# clock_core.net
KiCad netlist of a schematic drawn in Altium Designer
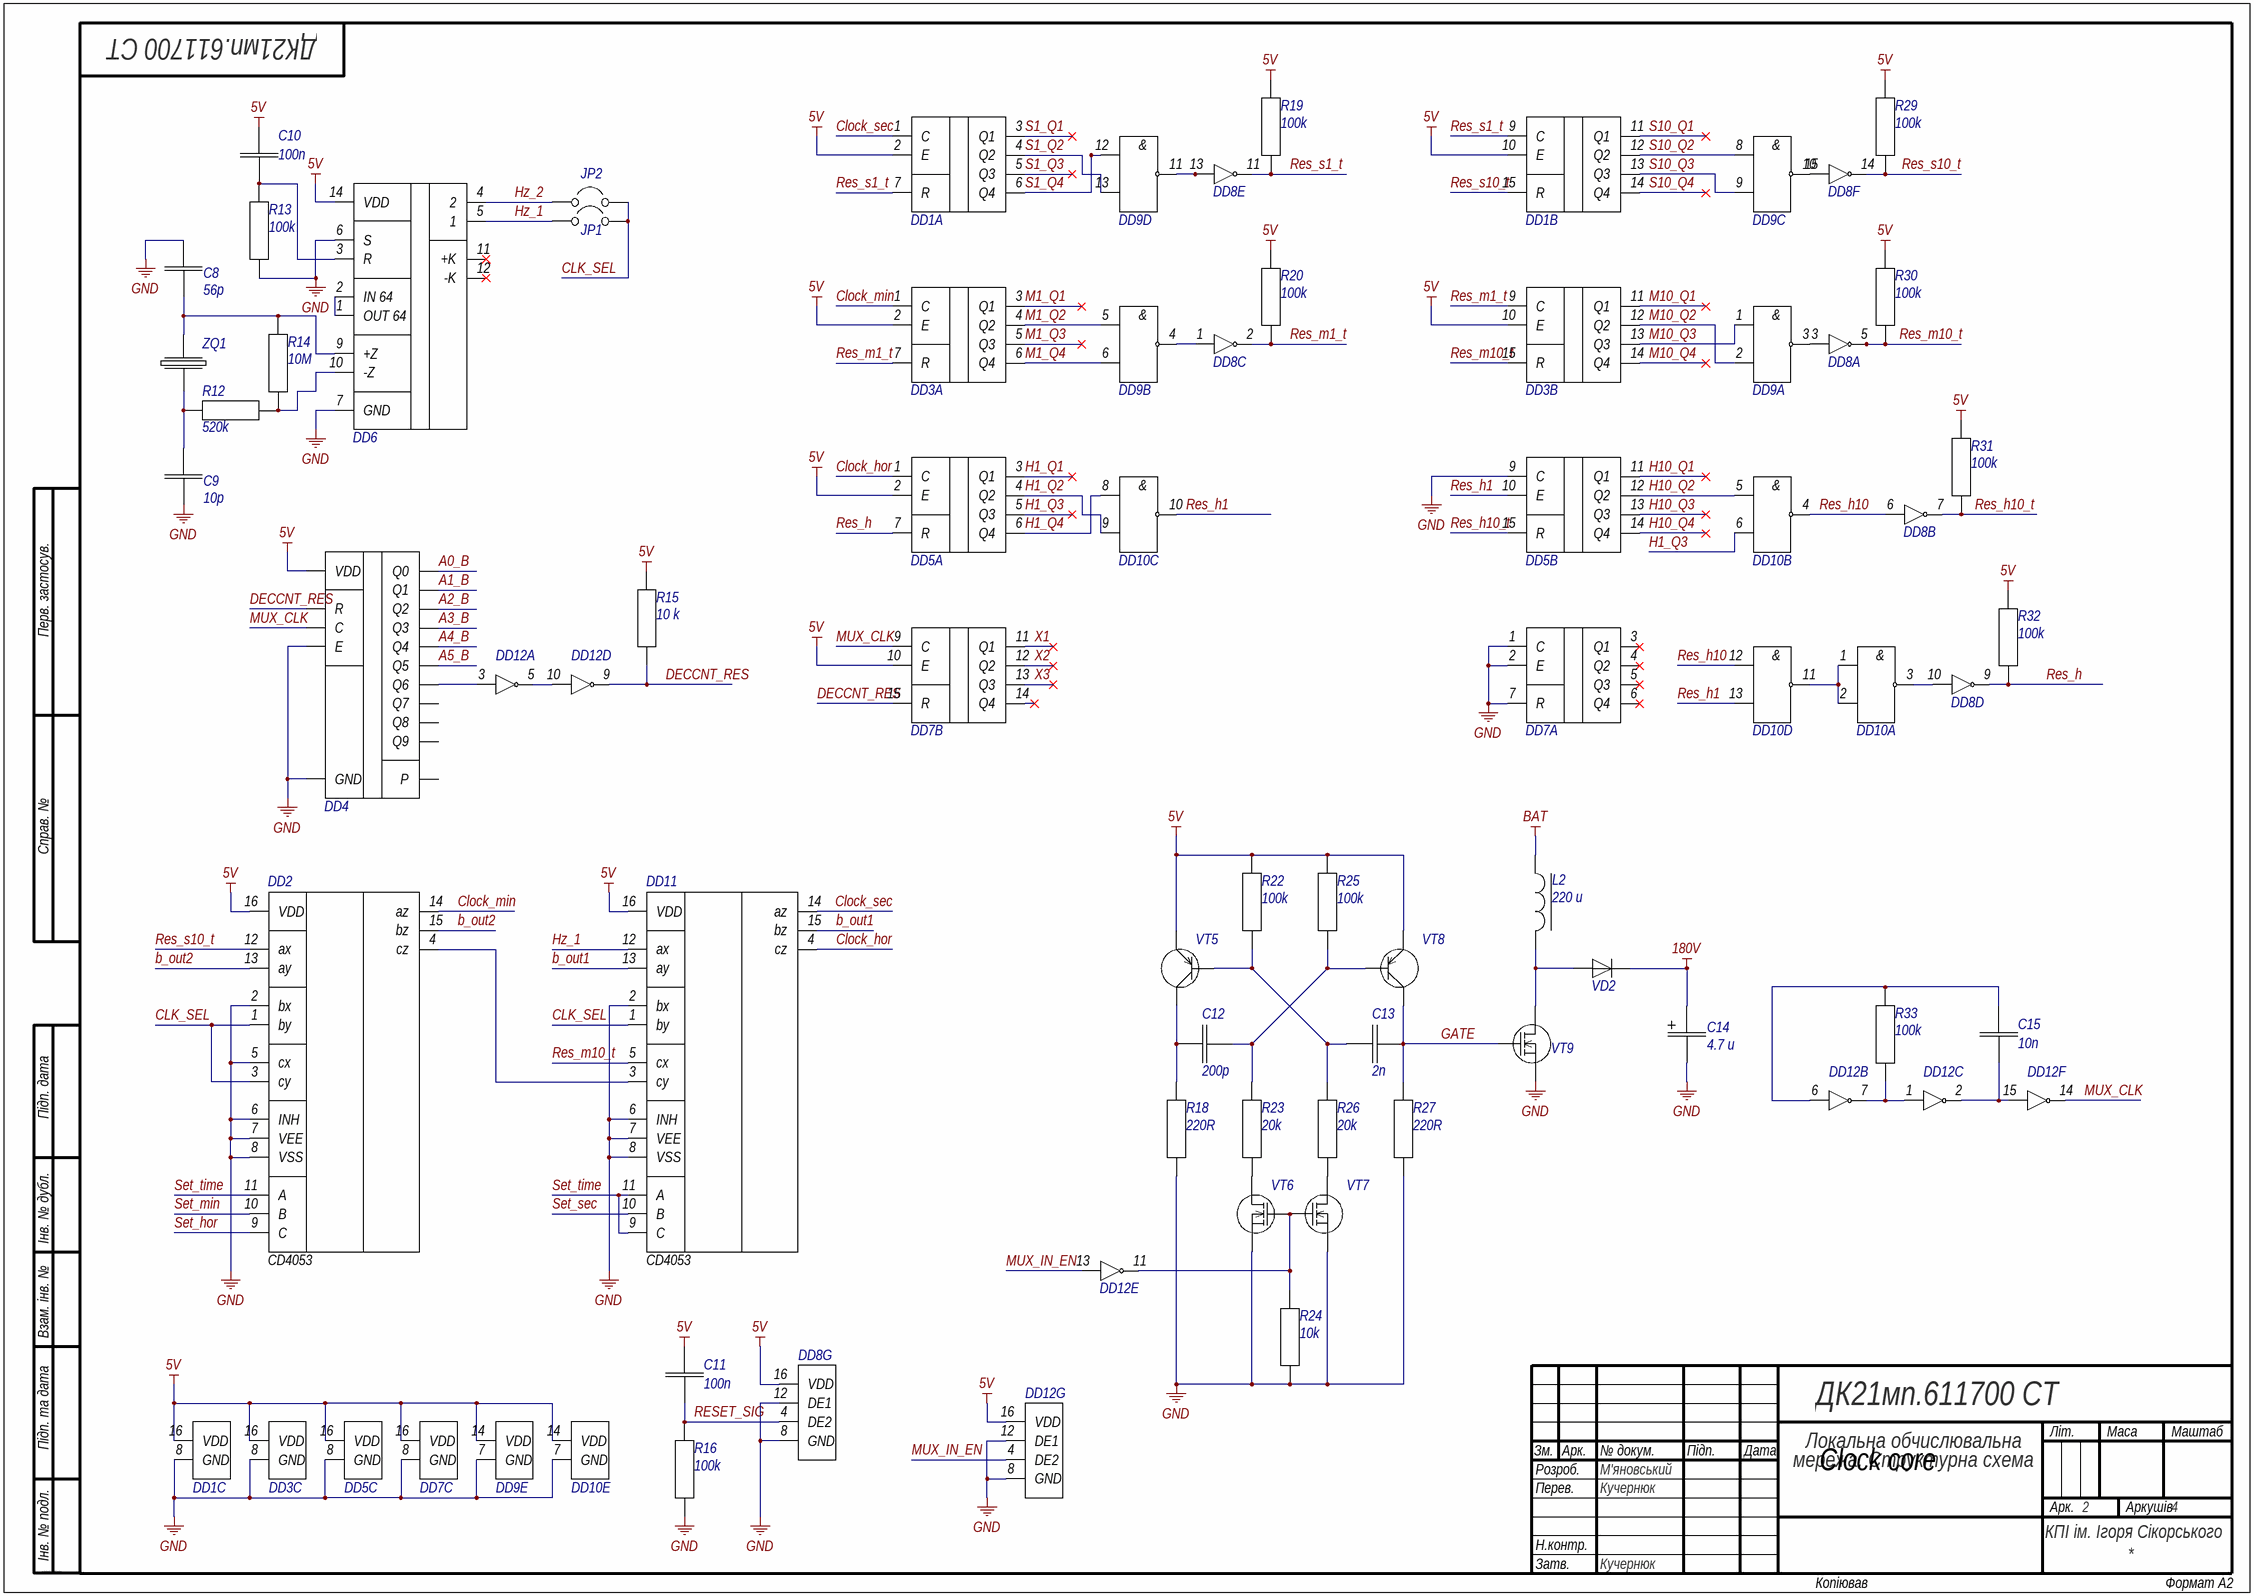
[diagram p0: clock_core.SchDoc]

(export (version "E")
  (design (tool "Eeschema 10.0.6"))
  (components
    (comp (ref "C8")
      (value "56p")
      (footprint "CAP_THT")
      (fields (field (name "Comment") "C"))
      (libsource (lib "Schlib1") (part "C"))
    )
    (comp (ref "C9")
      (value "10p")
      (footprint "CAP_THT")
      (fields (field (name "Comment") "C"))
      (libsource (lib "Schlib1") (part "C"))
    )
    (comp (ref "C10")
      (value "100n")
      (footprint "CAP_THT")
      (fields (field (name "Comment") "C"))
      (libsource (lib "Schlib1") (part "C"))
    )
    (comp (ref "C11")
      (value "100n")
      (footprint "CAP_THT")
      (fields (field (name "Comment") "C"))
      (libsource (lib "Schlib1") (part "C"))
    )
    (comp (ref "C12")
      (value "200p")
      (footprint "CAP_THT")
      (fields (field (name "Comment") "C"))
      (libsource (lib "Schlib1") (part "C"))
    )
    (comp (ref "C13")
      (value "2n")
      (footprint "CAP_THT")
      (fields (field (name "Comment") "C"))
      (libsource (lib "Schlib1") (part "C"))
    )
    (comp (ref "C14")
      (value "4.7 u")
      (footprint "CAP_HIGH_VOLT")
      (fields (field (name "Comment") "C+"))
      (libsource (lib "Schlib1") (part "C+"))
    )
    (comp (ref "C15")
      (value "10n")
      (footprint "CAP_THT")
      (fields (field (name "Comment") "C"))
      (libsource (lib "Schlib1") (part "C"))
    )
    (comp (ref "DD1") (value "К561ИЕ10") (footprint "DIP-16") (libsource (lib "Schlib1") (part "К561ИЕ10")))
    (comp (ref "DD2")
      (value "CD4053")
      (footprint "DIP-16")
      (fields (field (name "NAME") "CD4053"))
      (libsource (lib "Schlib1") (part "CD4053"))
    )
    (comp (ref "DD3") (value "К561ИЕ10") (footprint "DIP-16") (libsource (lib "Schlib1") (part "К561ИЕ10")))
    (comp (ref "DD4") (value "К561ИЕ8") (footprint "DIP-16") (libsource (lib "Schlib1") (part "К561ИЕ8")))
    (comp (ref "DD5") (value "К561ИЕ10") (footprint "DIP-16") (libsource (lib "Schlib1") (part "К561ИЕ10")))
    (comp (ref "DD6") (value "К176ИЕ5") (footprint "DIP-14") (libsource (lib "Schlib1") (part "К176ИЕ5")))
    (comp (ref "DD7") (value "К561ИЕ10") (footprint "DIP-16") (libsource (lib "Schlib1") (part "К561ИЕ10")))
    (comp (ref "DD8") (value "К561ЛН1") (footprint "DIP-16") (libsource (lib "Schlib1") (part "К561ЛН1")))
    (comp (ref "DD9") (value "К561ЛА7") (footprint "DIP-14") (libsource (lib "Schlib1") (part "К561ЛА7")))
    (comp (ref "DD10") (value "К561ЛА7") (footprint "DIP-14") (libsource (lib "Schlib1") (part "К561ЛА7")))
    (comp (ref "DD11")
      (value "CD4053")
      (footprint "DIP-16")
      (fields (field (name "NAME") "CD4053"))
      (libsource (lib "Schlib1") (part "CD4053"))
    )
    (comp (ref "DD12") (value "К561ЛН1") (footprint "DIP-16") (libsource (lib "Schlib1") (part "К561ЛН1")))
    (comp (ref "JP1") (value "Jumper") (footprint "JP") (libsource (lib "Schlib1") (part "Jumper")))
    (comp (ref "JP2") (value "Jumper") (footprint "JP") (libsource (lib "Schlib1") (part "Jumper")))
    (comp (ref "L2")
      (value "220 u")
      (footprint "IND")
      (fields (field (name "Comment") "L"))
      (libsource (lib "Schlib1") (part "L"))
    )
    (comp (ref "R12")
      (value "520k")
      (footprint "RES-DIP-V")
      (fields (field (name "Comment") "R"))
      (libsource (lib "") (part "R_1"))
    )
    (comp (ref "R13")
      (value "100k")
      (footprint "RES-DIP")
      (fields (field (name "Comment") "R"))
      (libsource (lib "Schlib1") (part "R"))
    )
    (comp (ref "R14")
      (value "10M")
      (footprint "RES-DIP-V")
      (fields (field (name "Comment") "R"))
      (libsource (lib "Schlib1") (part "R"))
    )
    (comp (ref "R15")
      (value "10 k")
      (footprint "RES-DIP")
      (fields (field (name "Comment") "R"))
      (libsource (lib "Schlib1") (part "R"))
    )
    (comp (ref "R16")
      (value "100k")
      (footprint "RES-DIP")
      (fields (field (name "Comment") "R"))
      (libsource (lib "Schlib1") (part "R"))
    )
    (comp (ref "R18")
      (value "220R")
      (footprint "RES-DIP-V")
      (fields (field (name "Comment") "R"))
      (libsource (lib "Schlib1") (part "R"))
    )
    (comp (ref "R19")
      (value "100k")
      (footprint "RES-DIP")
      (fields (field (name "Comment") "R"))
      (libsource (lib "Schlib1") (part "R"))
    )
    (comp (ref "R20")
      (value "100k")
      (footprint "RES-DIP")
      (fields (field (name "Comment") "R"))
      (libsource (lib "Schlib1") (part "R"))
    )
    (comp (ref "R22")
      (value "100k")
      (footprint "RES-DIP-V")
      (fields (field (name "Comment") "R"))
      (libsource (lib "Schlib1") (part "R"))
    )
    (comp (ref "R23")
      (value "20k")
      (footprint "RES-DIP-V")
      (fields (field (name "Comment") "R"))
      (libsource (lib "Schlib1") (part "R"))
    )
    (comp (ref "R24")
      (value "10k")
      (footprint "RES-DIP")
      (fields (field (name "Comment") "R"))
      (libsource (lib "Schlib1") (part "R"))
    )
    (comp (ref "R25")
      (value "100k")
      (footprint "RES-DIP-V")
      (fields (field (name "Comment") "R"))
      (libsource (lib "Schlib1") (part "R"))
    )
    (comp (ref "R26")
      (value "20k")
      (footprint "RES-DIP-V")
      (fields (field (name "Comment") "R"))
      (libsource (lib "Schlib1") (part "R"))
    )
    (comp (ref "R27")
      (value "220R")
      (footprint "RES-DIP-V")
      (fields (field (name "Comment") "R"))
      (libsource (lib "Schlib1") (part "R"))
    )
    (comp (ref "R29")
      (value "100k")
      (footprint "RES-DIP")
      (fields (field (name "Comment") "R"))
      (libsource (lib "Schlib1") (part "R"))
    )
    (comp (ref "R30")
      (value "100k")
      (footprint "RES-DIP")
      (fields (field (name "Comment") "R"))
      (libsource (lib "Schlib1") (part "R"))
    )
    (comp (ref "R31")
      (value "100k")
      (footprint "RES-DIP")
      (fields (field (name "Comment") "R"))
      (libsource (lib "") (part "R_2"))
    )
    (comp (ref "R32")
      (value "100k")
      (footprint "RES-DIP")
      (fields (field (name "Comment") "R"))
      (libsource (lib "Schlib1") (part "R"))
    )
    (comp (ref "R33")
      (value "100k")
      (footprint "RES-DIP")
      (fields (field (name "Comment") "R"))
      (libsource (lib "Schlib1") (part "R"))
    )
    (comp (ref "VD2") (value "1N4148") (footprint "1N4148") (libsource (lib "Schlib1") (part "1N4148")))
    (comp (ref "VT5") (value "BC327") (footprint "BC327") (libsource (lib "Schlib1") (part "BC327")))
    (comp (ref "VT6") (value "2N7000") (footprint "2N7000") (libsource (lib "Schlib1") (part "2N7000")))
    (comp (ref "VT7") (value "2N7000") (footprint "2N7000") (libsource (lib "Schlib1") (part "2N7000")))
    (comp (ref "VT8") (value "BC327") (footprint "BC327") (libsource (lib "Schlib1") (part "BC327")))
    (comp (ref "VT9") (value "IRF840") (footprint "IRF840") (libsource (lib "Schlib1") (part "IRF840")))
    (comp (ref "ZQ1") (value "HZ") (footprint "HZ") (libsource (lib "Schlib1") (part "HZ")))
  )
  (nets
    (net (code "1") (name "/A0_B") (class "Default")
      (node (ref "DD4") (pin "3") (pinfunction "Q0_3") (pintype "passive"))
    )
    (net (code "2") (name "/A1_B") (class "Default")
      (node (ref "DD4") (pin "2") (pinfunction "Q1_2") (pintype "passive"))
    )
    (net (code "3") (name "/A2_B") (class "Default")
      (node (ref "DD4") (pin "4") (pinfunction "Q2_4") (pintype "passive"))
    )
    (net (code "4") (name "/A3_B") (class "Default")
      (node (ref "DD4") (pin "7") (pinfunction "Q3_7") (pintype "passive"))
    )
    (net (code "5") (name "/A4_B") (class "Default")
      (node (ref "DD4") (pin "10") (pinfunction "Q4_10") (pintype "passive"))
    )
    (net (code "6") (name "/A5_B") (class "Default")
      (node (ref "DD4") (pin "1") (pinfunction "Q5_1") (pintype "passive"))
    )
    (net (code "7") (name "/CLK_SEL") (class "Default")
      (node (ref "DD11") (pin "1") (pinfunction "by_1") (pintype "passive"))
      (node (ref "DD2") (pin "1") (pinfunction "by_1") (pintype "passive"))
      (node (ref "DD2") (pin "3") (pinfunction "cy_3") (pintype "passive"))
      (node (ref "JP1") (pin "2") (pinfunction "2_2") (pintype "passive"))
      (node (ref "JP2") (pin "2") (pinfunction "2_2") (pintype "passive"))
    )
    (net (code "8") (name "/Clock_hor") (class "Default")
      (node (ref "DD11") (pin "4") (pinfunction "cz_4") (pintype "passive"))
      (node (ref "DD5") (pin "1") (pinfunction "C_1") (pintype "passive"))
    )
    (net (code "9") (name "/Clock_min") (class "Default")
      (node (ref "DD2") (pin "14") (pinfunction "az_14") (pintype "passive"))
      (node (ref "DD3") (pin "1") (pinfunction "C_1") (pintype "passive"))
    )
    (net (code "10") (name "/Clock_sec") (class "Default")
      (node (ref "DD1") (pin "1") (pinfunction "C_1") (pintype "passive"))
      (node (ref "DD11") (pin "14") (pinfunction "az_14") (pintype "passive"))
    )
    (net (code "11") (name "/DECCNT_RES") (class "Default")
      (node (ref "DD12") (pin "9") (pinfunction "OUT4_9") (pintype "passive"))
      (node (ref "DD4") (pin "15") (pinfunction "R_15") (pintype "passive"))
      (node (ref "DD7") (pin "15") (pinfunction "R_15") (pintype "passive"))
      (node (ref "R15") (pin "1") (pinfunction "1_1") (pintype "passive"))
    )
    (net (code "12") (name "/GATE") (class "Default")
      (node (ref "C13") (pin "2") (pinfunction "2_2") (pintype "passive"))
      (node (ref "R27") (pin "2") (pinfunction "2_2") (pintype "passive"))
      (node (ref "VT8") (pin "1") (pinfunction "C_1") (pintype "passive"))
      (node (ref "VT9") (pin "1") (pinfunction "G_1") (pintype "passive"))
    )
    (net (code "13") (name "/H1_Q1") (class "Default")
      (node (ref "DD5") (pin "3") (pinfunction "Q1_3") (pintype "passive+no_connect"))
    )
    (net (code "14") (name "/H1_Q2") (class "Default")
      (node (ref "DD10") (pin "9") (pinfunction "2_9") (pintype "passive"))
      (node (ref "DD5") (pin "4") (pinfunction "Q2_4") (pintype "passive"))
    )
    (net (code "15") (name "/H1_Q3") (class "Default")
      (node (ref "DD10") (pin "6") (pinfunction "2_6") (pintype "passive"))
      (node (ref "DD5") (pin "5") (pinfunction "Q3_5") (pintype "passive"))
    )
    (net (code "16") (name "/H1_Q4") (class "Default")
      (node (ref "DD10") (pin "8") (pinfunction "1_8") (pintype "passive"))
      (node (ref "DD5") (pin "6") (pinfunction "Q4_6") (pintype "passive"))
    )
    (net (code "17") (name "/H10_Q1") (class "Default")
      (node (ref "DD5") (pin "11") (pinfunction "Q1_11") (pintype "passive+no_connect"))
    )
    (net (code "18") (name "/H10_Q2") (class "Default")
      (node (ref "DD10") (pin "5") (pinfunction "1_5") (pintype "passive"))
      (node (ref "DD5") (pin "12") (pinfunction "Q2_12") (pintype "passive"))
    )
    (net (code "19") (name "/H10_Q3") (class "Default")
      (node (ref "DD5") (pin "13") (pinfunction "Q3_13") (pintype "passive+no_connect"))
    )
    (net (code "20") (name "/H10_Q4") (class "Default")
      (node (ref "DD5") (pin "14") (pinfunction "Q4_14") (pintype "passive+no_connect"))
    )
    (net (code "21") (name "/Hz_1") (class "Default")
      (node (ref "DD11") (pin "12") (pinfunction "ax_12") (pintype "passive"))
      (node (ref "DD6") (pin "5") (pinfunction "1_5") (pintype "passive"))
      (node (ref "JP1") (pin "1") (pinfunction "1_1") (pintype "passive"))
    )
    (net (code "22") (name "/Hz_2") (class "Default")
      (node (ref "DD6") (pin "4") (pinfunction "2_4") (pintype "passive"))
      (node (ref "JP2") (pin "1") (pinfunction "1_1") (pintype "passive"))
    )
    (net (code "23") (name "/M1_Q1") (class "Default")
      (node (ref "DD3") (pin "3") (pinfunction "Q1_3") (pintype "passive+no_connect"))
    )
    (net (code "24") (name "/M1_Q2") (class "Default")
      (node (ref "DD3") (pin "4") (pinfunction "Q2_4") (pintype "passive"))
      (node (ref "DD9") (pin "5") (pinfunction "1_5") (pintype "passive"))
    )
    (net (code "25") (name "/M1_Q3") (class "Default")
      (node (ref "DD3") (pin "5") (pinfunction "Q3_5") (pintype "passive+no_connect"))
    )
    (net (code "26") (name "/M1_Q4") (class "Default")
      (node (ref "DD3") (pin "6") (pinfunction "Q4_6") (pintype "passive"))
      (node (ref "DD9") (pin "6") (pinfunction "2_6") (pintype "passive"))
    )
    (net (code "27") (name "/M10_Q1") (class "Default")
      (node (ref "DD3") (pin "11") (pinfunction "Q1_11") (pintype "passive+no_connect"))
    )
    (net (code "28") (name "/M10_Q2") (class "Default")
      (node (ref "DD3") (pin "12") (pinfunction "Q2_12") (pintype "passive"))
      (node (ref "DD9") (pin "2") (pinfunction "2_2") (pintype "passive"))
    )
    (net (code "29") (name "/M10_Q3") (class "Default")
      (node (ref "DD3") (pin "13") (pinfunction "Q3_13") (pintype "passive"))
      (node (ref "DD9") (pin "1") (pinfunction "1_1") (pintype "passive"))
    )
    (net (code "30") (name "/M10_Q4") (class "Default")
      (node (ref "DD3") (pin "14") (pinfunction "Q4_14") (pintype "passive+no_connect"))
    )
    (net (code "31") (name "/MUX_CLK") (class "Default")
      (node (ref "DD12") (pin "14") (pinfunction "OUT6_14") (pintype "passive"))
      (node (ref "DD4") (pin "14") (pinfunction "C_14") (pintype "passive"))
      (node (ref "DD7") (pin "9") (pinfunction "C_9") (pintype "passive"))
    )
    (net (code "32") (name "/MUX_IN_EN") (class "Default")
      (node (ref "DD12") (pin "13") (pinfunction "IN5_13") (pintype "passive"))
      (node (ref "DD12") (pin "4") (pinfunction "DE2_4") (pintype "passive"))
    )
    (net (code "33") (name "/RESET_SIG") (class "Default")
      (node (ref "C11") (pin "1") (pinfunction "1_1") (pintype "passive"))
      (node (ref "DD8") (pin "4") (pinfunction "DE2_4") (pintype "passive"))
      (node (ref "R16") (pin "2") (pinfunction "2_2") (pintype "passive"))
    )
    (net (code "34") (name "/Res_h") (class "Default")
      (node (ref "DD5") (pin "7") (pinfunction "R_7") (pintype "passive"))
      (node (ref "DD8") (pin "9") (pinfunction "OUT4_9") (pintype "passive"))
      (node (ref "R32") (pin "1") (pinfunction "1_1") (pintype "passive"))
    )
    (net (code "35") (name "/Res_h1") (class "Default")
      (node (ref "DD10") (pin "10") (pinfunction "3_10") (pintype "passive"))
      (node (ref "DD10") (pin "13") (pinfunction "2_13") (pintype "passive"))
      (node (ref "DD5") (pin "10") (pinfunction "E_10") (pintype "passive"))
    )
    (net (code "36") (name "/Res_h10") (class "Default")
      (node (ref "DD10") (pin "12") (pinfunction "1_12") (pintype "passive"))
      (node (ref "DD10") (pin "4") (pinfunction "3_4") (pintype "passive"))
      (node (ref "DD8") (pin "6") (pinfunction "IN2_6") (pintype "passive"))
    )
    (net (code "37") (name "/Res_h10_t") (class "Default")
      (node (ref "DD5") (pin "15") (pinfunction "R_15") (pintype "passive"))
      (node (ref "DD8") (pin "7") (pinfunction "OUT2_7") (pintype "passive"))
      (node (ref "R31") (pin "2") (pinfunction "2_2") (pintype "passive"))
    )
    (net (code "38") (name "/Res_m1_t") (class "Default")
      (node (ref "DD3") (pin "7") (pinfunction "R_7") (pintype "passive"))
      (node (ref "DD3") (pin "9") (pinfunction "C_9") (pintype "passive"))
      (node (ref "DD8") (pin "2") (pinfunction "OUT3_2") (pintype "passive"))
      (node (ref "R20") (pin "1") (pinfunction "1_1") (pintype "passive"))
    )
    (net (code "39") (name "/Res_m10_t") (class "Default")
      (node (ref "DD11") (pin "5") (pinfunction "cx_5") (pintype "passive"))
      (node (ref "DD3") (pin "15") (pinfunction "R_15") (pintype "passive"))
      (node (ref "DD8") (pin "5") (pinfunction "OUT1_5") (pintype "passive"))
      (node (ref "R30") (pin "1") (pinfunction "1_1") (pintype "passive"))
    )
    (net (code "40") (name "/Res_s1_t") (class "Default")
      (node (ref "DD1") (pin "7") (pinfunction "R_7") (pintype "passive"))
      (node (ref "DD1") (pin "9") (pinfunction "C_9") (pintype "passive"))
      (node (ref "DD8") (pin "11") (pinfunction "OUT5_11") (pintype "passive"))
      (node (ref "R19") (pin "1") (pinfunction "1_1") (pintype "passive"))
    )
    (net (code "41") (name "/Res_s10_t") (class "Default")
      (node (ref "DD1") (pin "15") (pinfunction "R_15") (pintype "passive"))
      (node (ref "DD2") (pin "12") (pinfunction "ax_12") (pintype "passive"))
      (node (ref "DD8") (pin "14") (pinfunction "OUT6_14") (pintype "passive"))
      (node (ref "R29") (pin "1") (pinfunction "1_1") (pintype "passive"))
    )
    (net (code "42") (name "/S1_Q1") (class "Default")
      (node (ref "DD1") (pin "3") (pinfunction "Q1_3") (pintype "passive+no_connect"))
    )
    (net (code "43") (name "/S1_Q2") (class "Default")
      (node (ref "DD1") (pin "4") (pinfunction "Q2_4") (pintype "passive"))
      (node (ref "DD9") (pin "13") (pinfunction "2_13") (pintype "passive"))
    )
    (net (code "44") (name "/S1_Q3") (class "Default")
      (node (ref "DD1") (pin "5") (pinfunction "Q3_5") (pintype "passive+no_connect"))
    )
    (net (code "45") (name "/S1_Q4") (class "Default")
      (node (ref "DD1") (pin "6") (pinfunction "Q4_6") (pintype "passive"))
      (node (ref "DD9") (pin "12") (pinfunction "1_12") (pintype "passive"))
    )
    (net (code "46") (name "/S10_Q1") (class "Default")
      (node (ref "DD1") (pin "11") (pinfunction "Q1_11") (pintype "passive+no_connect"))
    )
    (net (code "47") (name "/S10_Q2") (class "Default")
      (node (ref "DD1") (pin "12") (pinfunction "Q2_12") (pintype "passive"))
      (node (ref "DD9") (pin "8") (pinfunction "1_8") (pintype "passive"))
    )
    (net (code "48") (name "/S10_Q3") (class "Default")
      (node (ref "DD1") (pin "13") (pinfunction "Q3_13") (pintype "passive"))
      (node (ref "DD9") (pin "9") (pinfunction "2_9") (pintype "passive"))
    )
    (net (code "49") (name "/S10_Q4") (class "Default")
      (node (ref "DD1") (pin "14") (pinfunction "Q4_14") (pintype "passive+no_connect"))
    )
    (net (code "50") (name "/Set_hor") (class "Default")
      (node (ref "DD2") (pin "9") (pinfunction "C_9") (pintype "passive"))
    )
    (net (code "51") (name "/Set_min") (class "Default")
      (node (ref "DD2") (pin "10") (pinfunction "B_10") (pintype "passive"))
    )
    (net (code "52") (name "/Set_sec") (class "Default")
      (node (ref "DD11") (pin "10") (pinfunction "B_10") (pintype "passive"))
    )
    (net (code "53") (name "/Set_time") (class "Default")
      (node (ref "DD11") (pin "11") (pinfunction "A_11") (pintype "passive"))
      (node (ref "DD11") (pin "9") (pinfunction "C_9") (pintype "passive"))
      (node (ref "DD2") (pin "11") (pinfunction "A_11") (pintype "passive"))
    )
    (net (code "54") (name "/X1") (class "Default")
      (node (ref "DD7") (pin "11") (pinfunction "Q1_11") (pintype "passive+no_connect"))
    )
    (net (code "55") (name "/X2") (class "Default")
      (node (ref "DD7") (pin "12") (pinfunction "Q2_12") (pintype "passive+no_connect"))
    )
    (net (code "56") (name "/X3") (class "Default")
      (node (ref "DD7") (pin "13") (pinfunction "Q3_13") (pintype "passive+no_connect"))
    )
    (net (code "57") (name "/b_out1") (class "Default")
      (node (ref "DD11") (pin "13") (pinfunction "ay_13") (pintype "passive"))
      (node (ref "DD11") (pin "15") (pinfunction "bz_15") (pintype "passive"))
    )
    (net (code "58") (name "/b_out2") (class "Default")
      (node (ref "DD2") (pin "13") (pinfunction "ay_13") (pintype "passive"))
      (node (ref "DD2") (pin "15") (pinfunction "bz_15") (pintype "passive"))
    )
    (net (code "59") (name "5V") (class "Default")
      (node (ref "C10") (pin "2") (pinfunction "2_2") (pintype "passive"))
      (node (ref "C11") (pin "2") (pinfunction "2_2") (pintype "passive"))
      (node (ref "DD1") (pin "10") (pinfunction "E_10") (pintype "passive"))
      (node (ref "DD1") (pin "16") (pinfunction "VDD_16") (pintype "passive"))
      (node (ref "DD1") (pin "2") (pinfunction "E_2") (pintype "passive"))
      (node (ref "DD10") (pin "14") (pinfunction "VDD_14") (pintype "passive"))
      (node (ref "DD11") (pin "16") (pinfunction "VDD_16") (pintype "passive"))
      (node (ref "DD12") (pin "16") (pinfunction "VDD_16") (pintype "passive"))
      (node (ref "DD2") (pin "16") (pinfunction "VDD_16") (pintype "passive"))
      (node (ref "DD3") (pin "10") (pinfunction "E_10") (pintype "passive"))
      (node (ref "DD3") (pin "16") (pinfunction "VDD_16") (pintype "passive"))
      (node (ref "DD3") (pin "2") (pinfunction "E_2") (pintype "passive"))
      (node (ref "DD4") (pin "16") (pinfunction "VDD_16") (pintype "passive"))
      (node (ref "DD5") (pin "16") (pinfunction "VDD_16") (pintype "passive"))
      (node (ref "DD5") (pin "2") (pinfunction "E_2") (pintype "passive"))
      (node (ref "DD6") (pin "14") (pinfunction "VDD_14") (pintype "passive"))
      (node (ref "DD7") (pin "10") (pinfunction "E_10") (pintype "passive"))
      (node (ref "DD7") (pin "16") (pinfunction "VDD_16") (pintype "passive"))
      (node (ref "DD8") (pin "16") (pinfunction "VDD_16") (pintype "passive"))
      (node (ref "DD9") (pin "14") (pinfunction "VDD_14") (pintype "passive"))
      (node (ref "R15") (pin "2") (pinfunction "2_2") (pintype "passive"))
      (node (ref "R19") (pin "2") (pinfunction "2_2") (pintype "passive"))
      (node (ref "R20") (pin "2") (pinfunction "2_2") (pintype "passive"))
      (node (ref "R22") (pin "2") (pinfunction "2_2") (pintype "passive"))
      (node (ref "R25") (pin "2") (pinfunction "2_2") (pintype "passive"))
      (node (ref "R29") (pin "2") (pinfunction "2_2") (pintype "passive"))
      (node (ref "R30") (pin "2") (pinfunction "2_2") (pintype "passive"))
      (node (ref "R31") (pin "1") (pinfunction "1_1") (pintype "passive"))
      (node (ref "R32") (pin "2") (pinfunction "2_2") (pintype "passive"))
      (node (ref "VT5") (pin "3") (pinfunction "E_3") (pintype "passive"))
      (node (ref "VT8") (pin "3") (pinfunction "E_3") (pintype "passive"))
    )
    (net (code "60") (name "180V") (class "Default")
      (node (ref "C14") (pin "1") (pinfunction "1_1") (pintype "passive"))
      (node (ref "VD2") (pin "1") (pinfunction "K_1") (pintype "passive"))
    )
    (net (code "61") (name "BAT") (class "Default")
      (node (ref "L2") (pin "1") (pinfunction "1_1") (pintype "passive"))
    )
    (net (code "62") (name "GND") (class "Default")
      (node (ref "C14") (pin "2") (pinfunction "2_2") (pintype "passive"))
      (node (ref "C8") (pin "2") (pinfunction "2_2") (pintype "passive"))
      (node (ref "C9") (pin "1") (pinfunction "1_1") (pintype "passive"))
      (node (ref "DD1") (pin "8") (pinfunction "GND_8") (pintype "passive"))
      (node (ref "DD10") (pin "7") (pinfunction "GND_7") (pintype "passive"))
      (node (ref "DD11") (pin "2") (pinfunction "bx_2") (pintype "passive"))
      (node (ref "DD11") (pin "6") (pinfunction "INH_6") (pintype "passive"))
      (node (ref "DD11") (pin "7") (pinfunction "VEE_7") (pintype "passive"))
      (node (ref "DD11") (pin "8") (pinfunction "VSS_8") (pintype "passive"))
      (node (ref "DD12") (pin "12") (pinfunction "DE1_12") (pintype "passive"))
      (node (ref "DD12") (pin "8") (pinfunction "GND_8") (pintype "passive"))
      (node (ref "DD2") (pin "2") (pinfunction "bx_2") (pintype "passive"))
      (node (ref "DD2") (pin "5") (pinfunction "cx_5") (pintype "passive"))
      (node (ref "DD2") (pin "6") (pinfunction "INH_6") (pintype "passive"))
      (node (ref "DD2") (pin "7") (pinfunction "VEE_7") (pintype "passive"))
      (node (ref "DD2") (pin "8") (pinfunction "VSS_8") (pintype "passive"))
      (node (ref "DD3") (pin "8") (pinfunction "GND_8") (pintype "passive"))
      (node (ref "DD4") (pin "13") (pinfunction "E_13") (pintype "passive"))
      (node (ref "DD4") (pin "8") (pinfunction "GND_8") (pintype "passive"))
      (node (ref "DD5") (pin "8") (pinfunction "GND_8") (pintype "passive"))
      (node (ref "DD5") (pin "9") (pinfunction "C_9") (pintype "passive"))
      (node (ref "DD6") (pin "6") (pinfunction "S_6") (pintype "passive"))
      (node (ref "DD6") (pin "7") (pinfunction "GND_7") (pintype "passive"))
      (node (ref "DD7") (pin "1") (pinfunction "C_1") (pintype "passive"))
      (node (ref "DD7") (pin "2") (pinfunction "E_2") (pintype "passive"))
      (node (ref "DD7") (pin "7") (pinfunction "R_7") (pintype "passive"))
      (node (ref "DD7") (pin "8") (pinfunction "GND_8") (pintype "passive"))
      (node (ref "DD8") (pin "12") (pinfunction "DE1_12") (pintype "passive"))
      (node (ref "DD8") (pin "8") (pinfunction "GND_8") (pintype "passive"))
      (node (ref "DD9") (pin "7") (pinfunction "GND_7") (pintype "passive"))
      (node (ref "R13") (pin "1") (pinfunction "1_1") (pintype "passive"))
      (node (ref "R16") (pin "1") (pinfunction "1_1") (pintype "passive"))
      (node (ref "R18") (pin "1") (pinfunction "1_1") (pintype "passive"))
      (node (ref "R24") (pin "1") (pinfunction "1_1") (pintype "passive"))
      (node (ref "R27") (pin "1") (pinfunction "1_1") (pintype "passive"))
      (node (ref "VT6") (pin "1") (pinfunction "S_1") (pintype "passive"))
      (node (ref "VT7") (pin "1") (pinfunction "S_1") (pintype "passive"))
      (node (ref "VT9") (pin "3") (pinfunction "S_3") (pintype "passive"))
    )
    (net (code "63") (name "Net-(C9-Pad2)") (class "Default")
      (node (ref "C9") (pin "2") (pinfunction "2_2") (pintype "passive"))
      (node (ref "R12") (pin "1") (pinfunction "1_1") (pintype "passive"))
      (node (ref "ZQ1") (pin "1") (pinfunction "1_1") (pintype "passive"))
    )
    (net (code "64") (name "Net-(DD6-+Z)") (class "Default")
      (node (ref "C8") (pin "1") (pinfunction "1_1") (pintype "passive"))
      (node (ref "DD6") (pin "9") (pinfunction "+Z_9") (pintype "passive"))
      (node (ref "R14") (pin "2") (pinfunction "2_2") (pintype "passive"))
      (node (ref "ZQ1") (pin "2") (pinfunction "2_2") (pintype "passive"))
    )
    (net (code "65") (name "Net-(DD6--Z)") (class "Default")
      (node (ref "DD6") (pin "10") (pinfunction "-Z_10") (pintype "passive"))
      (node (ref "R12") (pin "2") (pinfunction "2_2") (pintype "passive"))
      (node (ref "R14") (pin "1") (pinfunction "1_1") (pintype "passive"))
    )
    (net (code "66") (name "Net-(DD6-IN_64)") (class "Default")
      (node (ref "DD6") (pin "1") (pinfunction "OUT_64_1") (pintype "passive"))
      (node (ref "DD6") (pin "2") (pinfunction "IN_64_2") (pintype "passive"))
    )
    (net (code "67") (name "Net-(DD6-R)") (class "Default")
      (node (ref "C10") (pin "1") (pinfunction "1_1") (pintype "passive"))
      (node (ref "DD6") (pin "3") (pinfunction "R_3") (pintype "passive"))
      (node (ref "R13") (pin "2") (pinfunction "2_2") (pintype "passive"))
    )
    (net (code "68") (name "Net-(DD8A-IN1)") (class "Default")
      (node (ref "DD8") (pin "3") (pinfunction "IN1_3") (pintype "passive"))
      (node (ref "DD9") (pin "3") (pinfunction "3_3") (pintype "passive"))
    )
    (net (code "69") (name "Net-(DD8C-IN3)") (class "Default")
      (node (ref "DD8") (pin "1") (pinfunction "IN3_1") (pintype "passive"))
      (node (ref "DD9") (pin "4") (pinfunction "3_4") (pintype "passive"))
    )
    (net (code "70") (name "Net-(DD8D-IN4)") (class "Default")
      (node (ref "DD10") (pin "3") (pinfunction "3_3") (pintype "passive"))
      (node (ref "DD8") (pin "10") (pinfunction "IN4_10") (pintype "passive"))
    )
    (net (code "71") (name "Net-(DD8E-IN5)") (class "Default")
      (node (ref "DD8") (pin "13") (pinfunction "IN5_13") (pintype "passive"))
      (node (ref "DD9") (pin "11") (pinfunction "3_11") (pintype "passive"))
    )
    (net (code "72") (name "Net-(DD8F-IN6)") (class "Default")
      (node (ref "DD8") (pin "15") (pinfunction "IN6_15") (pintype "passive"))
      (node (ref "DD9") (pin "10") (pinfunction "3_10") (pintype "passive"))
    )
    (net (code "73") (name "Net-(DD10D-3)") (class "Default")
      (node (ref "DD10") (pin "1") (pinfunction "1_1") (pintype "passive"))
      (node (ref "DD10") (pin "11") (pinfunction "3_11") (pintype "passive"))
      (node (ref "DD10") (pin "2") (pinfunction "2_2") (pintype "passive"))
    )
    (net (code "74") (name "Net-(DD11-cy)") (class "Default")
      (node (ref "DD11") (pin "3") (pinfunction "cy_3") (pintype "passive"))
      (node (ref "DD2") (pin "4") (pinfunction "cz_4") (pintype "passive"))
    )
    (net (code "75") (name "Net-(DD12A-IN1)") (class "Default")
      (node (ref "DD12") (pin "3") (pinfunction "IN1_3") (pintype "passive"))
      (node (ref "DD4") (pin "5") (pinfunction "Q6_5") (pintype "passive"))
    )
    (net (code "76") (name "Net-(DD12A-OUT1)") (class "Default")
      (node (ref "DD12") (pin "10") (pinfunction "IN4_10") (pintype "passive"))
      (node (ref "DD12") (pin "5") (pinfunction "OUT1_5") (pintype "passive"))
    )
    (net (code "77") (name "Net-(DD12B-IN2)") (class "Default")
      (node (ref "C15") (pin "1") (pinfunction "1_1") (pintype "passive"))
      (node (ref "DD12") (pin "6") (pinfunction "IN2_6") (pintype "passive"))
      (node (ref "R33") (pin "2") (pinfunction "2_2") (pintype "passive"))
    )
    (net (code "78") (name "Net-(DD12B-OUT2)") (class "Default")
      (node (ref "DD12") (pin "1") (pinfunction "IN3_1") (pintype "passive"))
      (node (ref "DD12") (pin "7") (pinfunction "OUT2_7") (pintype "passive"))
      (node (ref "R33") (pin "1") (pinfunction "1_1") (pintype "passive"))
    )
    (net (code "79") (name "Net-(DD12C-OUT3)") (class "Default")
      (node (ref "C15") (pin "2") (pinfunction "2_2") (pintype "passive"))
      (node (ref "DD12") (pin "15") (pinfunction "IN6_15") (pintype "passive"))
      (node (ref "DD12") (pin "2") (pinfunction "OUT3_2") (pintype "passive"))
    )
    (net (code "80") (name "Net-(DD12E-OUT5)") (class "Default")
      (node (ref "DD12") (pin "11") (pinfunction "OUT5_11") (pintype "passive"))
      (node (ref "R24") (pin "2") (pinfunction "2_2") (pintype "passive"))
      (node (ref "VT6") (pin "2") (pinfunction "G_2") (pintype "passive"))
      (node (ref "VT7") (pin "2") (pinfunction "G_2") (pintype "passive"))
    )
    (net (code "81") (name "Net-(VD2-A)") (class "Default")
      (node (ref "L2") (pin "2") (pinfunction "2_2") (pintype "passive"))
      (node (ref "VD2") (pin "2") (pinfunction "A_2") (pintype "passive"))
      (node (ref "VT9") (pin "2") (pinfunction "D_2") (pintype "passive"))
    )
    (net (code "82") (name "Net-(VT5-B)") (class "Default")
      (node (ref "C13") (pin "1") (pinfunction "1_1") (pintype "passive"))
      (node (ref "R22") (pin "1") (pinfunction "1_1") (pintype "passive"))
      (node (ref "R26") (pin "2") (pinfunction "2_2") (pintype "passive"))
      (node (ref "VT5") (pin "2") (pinfunction "B_2") (pintype "passive"))
    )
    (net (code "83") (name "Net-(VT5-C)") (class "Default")
      (node (ref "C12") (pin "1") (pinfunction "1_1") (pintype "passive"))
      (node (ref "R18") (pin "2") (pinfunction "2_2") (pintype "passive"))
      (node (ref "VT5") (pin "1") (pinfunction "C_1") (pintype "passive"))
    )
    (net (code "84") (name "Net-(VT6-D)") (class "Default")
      (node (ref "R23") (pin "1") (pinfunction "1_1") (pintype "passive"))
      (node (ref "VT6") (pin "3") (pinfunction "D_3") (pintype "passive"))
    )
    (net (code "85") (name "Net-(VT7-D)") (class "Default")
      (node (ref "R26") (pin "1") (pinfunction "1_1") (pintype "passive"))
      (node (ref "VT7") (pin "3") (pinfunction "D_3") (pintype "passive"))
    )
    (net (code "86") (name "Net-(VT8-B)") (class "Default")
      (node (ref "C12") (pin "2") (pinfunction "2_2") (pintype "passive"))
      (node (ref "R23") (pin "2") (pinfunction "2_2") (pintype "passive"))
      (node (ref "R25") (pin "1") (pinfunction "1_1") (pintype "passive"))
      (node (ref "VT8") (pin "2") (pinfunction "B_2") (pintype "passive"))
    )
    (net (code "87") (name "unconnected-(DD4-P-Pad12)") (class "Default")
      (node (ref "DD4") (pin "12") (pinfunction "P_12") (pintype "passive"))
    )
    (net (code "88") (name "unconnected-(DD4-Q7-Pad6)") (class "Default")
      (node (ref "DD4") (pin "6") (pinfunction "Q7_6") (pintype "passive"))
    )
    (net (code "89") (name "unconnected-(DD4-Q8-Pad9)") (class "Default")
      (node (ref "DD4") (pin "9") (pinfunction "Q8_9") (pintype "passive"))
    )
    (net (code "90") (name "unconnected-(DD4-Q9-Pad11)") (class "Default")
      (node (ref "DD4") (pin "11") (pinfunction "Q9_11") (pintype "passive"))
    )
    (net (code "91") (name "unconnected-(DD6-+K-Pad11)") (class "Default")
      (node (ref "DD6") (pin "11") (pinfunction "+K_11") (pintype "passive+no_connect"))
    )
    (net (code "92") (name "unconnected-(DD6--K-Pad12)") (class "Default")
      (node (ref "DD6") (pin "12") (pinfunction "-K_12") (pintype "passive+no_connect"))
    )
    (net (code "93") (name "unconnected-(DD7A-Q1-Pad3)") (class "Default")
      (node (ref "DD7") (pin "3") (pinfunction "Q1_3") (pintype "passive+no_connect"))
    )
    (net (code "94") (name "unconnected-(DD7A-Q2-Pad4)") (class "Default")
      (node (ref "DD7") (pin "4") (pinfunction "Q2_4") (pintype "passive+no_connect"))
    )
    (net (code "95") (name "unconnected-(DD7A-Q3-Pad5)") (class "Default")
      (node (ref "DD7") (pin "5") (pinfunction "Q3_5") (pintype "passive+no_connect"))
    )
    (net (code "96") (name "unconnected-(DD7A-Q4-Pad6)") (class "Default")
      (node (ref "DD7") (pin "6") (pinfunction "Q4_6") (pintype "passive+no_connect"))
    )
    (net (code "97") (name "unconnected-(DD7B-Q4-Pad14)") (class "Default")
      (node (ref "DD7") (pin "14") (pinfunction "Q4_14") (pintype "passive+no_connect"))
    )
  )
)
